# FUSE_AND_I_SENSE.net
KiCad netlist of a schematic drawn in Altium Designer
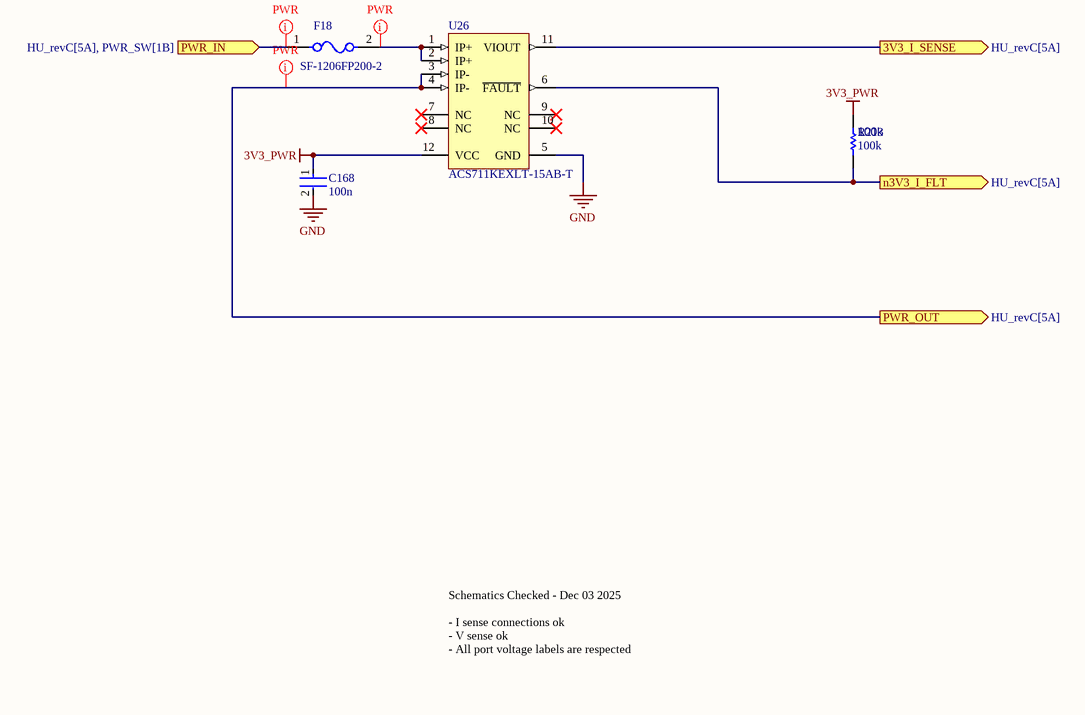
[diagram p0: FUSE_AND_I_SENSE.SchDoc]

(export (version "E")
  (design (tool "Eeschema 10.0.6"))
  (components
    (comp (ref "C168")
      (value "100n")
      (footprint "FP-0402-L_1_0_0_05-W_0_5-IPC_A")
      (description "LARGE PADS, 0402 CAP, CHANGE COMMENT TO MATCH REAL P/N")
      (libsource (lib "Space Concordia") (part "b4654b650e69147ec39a6b967a45e02"))
    )
    (comp (ref "F18")
      (value "SF-1206FP200-2")
      (footprint "FP-SF-1206FP-MFG")
      (description "FUSE BOARD MOUNT 2A 63VDC 1206")
      (libsource (lib "Altium Content Vault") (part "5bcf9b9f640e542cf0359d10258e979"))
    )
    (comp (ref "R213")
      (value "100k")
      (footprint "R0603B")
      (description "Resistor")
      (fields (field (name "ALTIUM_VALUE") "100k"))
      (libsource (lib "Space Concordia") (part "Resistor"))
    )
    (comp (ref "U26")
      (value "ACS711KEXLT-15AB-T")
      (footprint "ALEG-EX-12_V")
      (libsource (lib "Altium Content Vault") (part "ALEG-ACS711-QFN-12"))
    )
  )
  (nets
    (net (code "1") (name "/3V3_I_SENSE") (class "Default")
      (node (ref "U26") (pin "11") (pinfunction "VIOUT_11") (pintype "output"))
    )
    (net (code "2") (name "/PWR_IN") (class "Default")
      (node (ref "F18") (pin "1") (pinfunction "1_1") (pintype "passive"))
    )
    (net (code "3") (name "/PWR_OUT") (class "Default")
      (node (ref "U26") (pin "3") (pinfunction "IP-_3") (pintype "input"))
      (node (ref "U26") (pin "4") (pinfunction "IP-_4") (pintype "input"))
    )
    (net (code "4") (name "/n3V3_I_FLT") (class "Default")
      (node (ref "R213") (pin "1") (pinfunction "1_1") (pintype "passive"))
      (node (ref "U26") (pin "6") (pinfunction "~{FAULT}_6") (pintype "output"))
    )
    (net (code "5") (name "3V3_PWR") (class "Default")
      (node (ref "C168") (pin "1") (pinfunction "1_1") (pintype "passive"))
      (node (ref "R213") (pin "2") (pinfunction "2_2") (pintype "passive"))
      (node (ref "U26") (pin "12") (pinfunction "VCC_12") (pintype "power_in"))
    )
    (net (code "6") (name "GND") (class "Default")
      (node (ref "C168") (pin "2") (pinfunction "2_2") (pintype "passive"))
      (node (ref "U26") (pin "5") (pinfunction "GND_5") (pintype "power_in"))
    )
    (net (code "7") (name "Net-(F18-Pad2)") (class "Default")
      (node (ref "F18") (pin "2") (pinfunction "2_2") (pintype "passive"))
      (node (ref "U26") (pin "1") (pinfunction "IP+_1") (pintype "input"))
      (node (ref "U26") (pin "2") (pinfunction "IP+_2") (pintype "input"))
    )
    (net (code "8") (name "unconnected-(U26-NC-Pad7)") (class "Default")
      (node (ref "U26") (pin "7") (pinfunction "NC_7") (pintype "passive+no_connect"))
    )
    (net (code "9") (name "unconnected-(U26-NC-Pad8)") (class "Default")
      (node (ref "U26") (pin "8") (pinfunction "NC_8") (pintype "passive+no_connect"))
    )
    (net (code "10") (name "unconnected-(U26-NC-Pad9)") (class "Default")
      (node (ref "U26") (pin "9") (pinfunction "NC_9") (pintype "passive+no_connect"))
    )
    (net (code "11") (name "unconnected-(U26-NC-Pad10)") (class "Default")
      (node (ref "U26") (pin "10") (pinfunction "NC_10") (pintype "passive+no_connect"))
    )
  )
)
